# Sheet2.net
KiCad netlist of a schematic drawn in Altium Designer
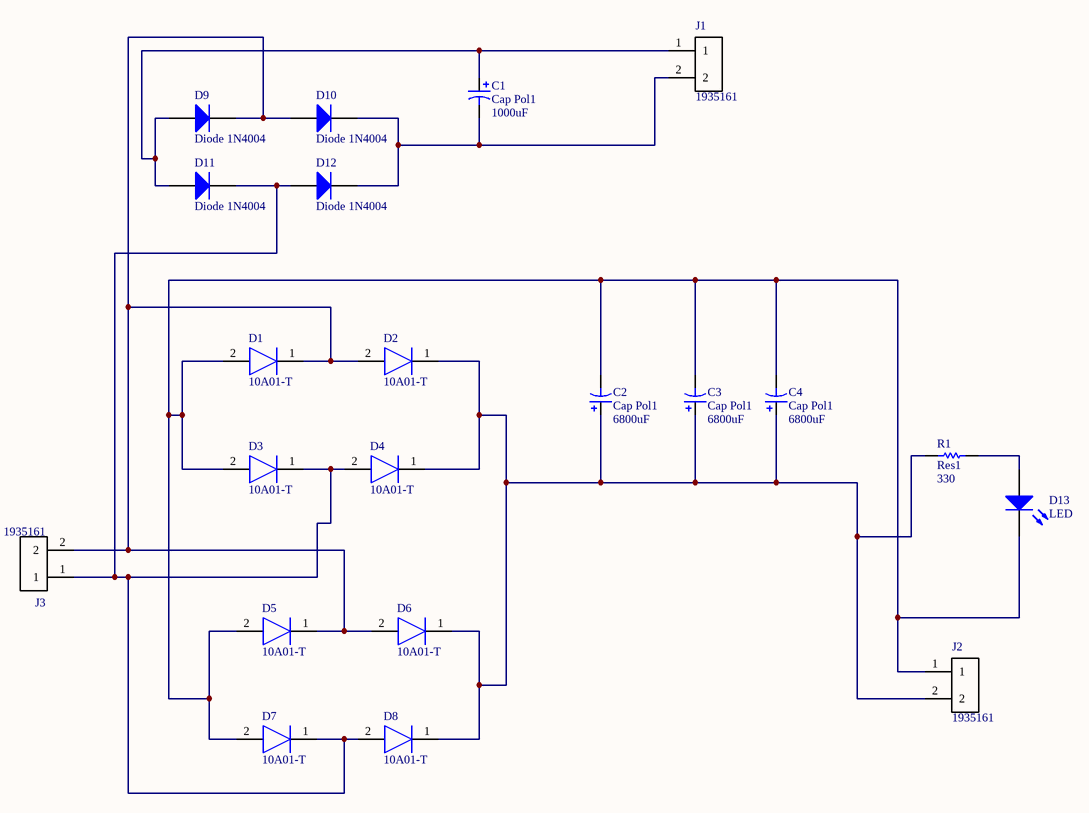
[diagram p0: Sheet2.SchDoc]

(export (version "E")
  (design (tool "Eeschema 10.0.6"))
  (components
    (comp (ref "C1")
      (value "Cap Pol1")
      (footprint "RB7.6-15")
      (description "Polarized Capacitor (Radial)")
      (fields (field (name "ALTIUM_VALUE") "1000uF") (field (name "PUBLISHER") "Altium Limited"))
      (libsource (lib "Miscellaneous Devices") (part "Cap Pol1"))
    )
    (comp (ref "C2")
      (value "Cap Pol1")
      (footprint "RB7.6-15")
      (description "Polarized Capacitor (Radial)")
      (fields (field (name "ALTIUM_VALUE") "6800uF") (field (name "PUBLISHER") "Altium Limited"))
      (libsource (lib "Miscellaneous Devices") (part "Cap Pol1"))
    )
    (comp (ref "C3")
      (value "Cap Pol1")
      (footprint "RB7.6-15")
      (description "Polarized Capacitor (Radial)")
      (fields (field (name "ALTIUM_VALUE") "6800uF") (field (name "PUBLISHER") "Altium Limited"))
      (libsource (lib "Miscellaneous Devices") (part "Cap Pol1"))
    )
    (comp (ref "C4")
      (value "Cap Pol1")
      (footprint "RB7.6-15")
      (description "Polarized Capacitor (Radial)")
      (fields (field (name "ALTIUM_VALUE") "6800uF") (field (name "PUBLISHER") "Altium Limited"))
      (libsource (lib "Miscellaneous Devices") (part "Cap Pol1"))
    )
    (comp (ref "D1")
      (value "10A01-T")
      (footprint "SamacSys:DIOAD4425W130L885D885")
      (description "Diode")
      (fields (field (name "MOUSER PART NUMBER") "621-10A01-T") (field (name "RS PART NUMBER") "9228248"))
      (libsource (lib "*") (part "10A01-T"))
    )
    (comp (ref "D2")
      (value "10A01-T")
      (footprint "SamacSys:DIOAD4425W130L885D885")
      (description "Diode")
      (fields (field (name "MOUSER PART NUMBER") "621-10A01-T") (field (name "RS PART NUMBER") "9228248"))
      (libsource (lib "*") (part "10A01-T"))
    )
    (comp (ref "D3")
      (value "10A01-T")
      (footprint "SamacSys:DIOAD4425W130L885D885")
      (description "Diode")
      (fields (field (name "MOUSER PART NUMBER") "621-10A01-T") (field (name "RS PART NUMBER") "9228248"))
      (libsource (lib "*") (part "10A01-T"))
    )
    (comp (ref "D4")
      (value "10A01-T")
      (footprint "SamacSys:DIOAD4425W130L885D885")
      (description "Diode")
      (fields (field (name "MOUSER PART NUMBER") "621-10A01-T") (field (name "RS PART NUMBER") "9228248"))
      (libsource (lib "*") (part "10A01-T"))
    )
    (comp (ref "D5")
      (value "10A01-T")
      (footprint "SamacSys:DIOAD4425W130L885D885")
      (description "Diode")
      (fields (field (name "MOUSER PART NUMBER") "621-10A01-T") (field (name "RS PART NUMBER") "9228248"))
      (libsource (lib "*") (part "10A01-T"))
    )
    (comp (ref "D6")
      (value "10A01-T")
      (footprint "SamacSys:DIOAD4425W130L885D885")
      (description "Diode")
      (fields (field (name "MOUSER PART NUMBER") "621-10A01-T") (field (name "RS PART NUMBER") "9228248"))
      (libsource (lib "*") (part "10A01-T"))
    )
    (comp (ref "D7")
      (value "10A01-T")
      (footprint "SamacSys:DIOAD4425W130L885D885")
      (description "Diode")
      (fields (field (name "MOUSER PART NUMBER") "621-10A01-T") (field (name "RS PART NUMBER") "9228248"))
      (libsource (lib "*") (part "10A01-T"))
    )
    (comp (ref "D8")
      (value "10A01-T")
      (footprint "SamacSys:DIOAD4425W130L885D885")
      (description "Diode")
      (fields (field (name "MOUSER PART NUMBER") "621-10A01-T") (field (name "RS PART NUMBER") "9228248"))
      (libsource (lib "*") (part "10A01-T"))
    )
    (comp (ref "D9")
      (value "Diode 1N4004")
      (footprint "DO-41")
      (description "1 Amp General Purpose Rectifier")
      (fields (field (name "PUBLISHER") "Altium Limited"))
      (libsource (lib "Miscellaneous Devices") (part "Diode 1N4004"))
    )
    (comp (ref "D10")
      (value "Diode 1N4004")
      (footprint "DO-41")
      (description "1 Amp General Purpose Rectifier")
      (fields (field (name "PUBLISHER") "Altium Limited"))
      (libsource (lib "Miscellaneous Devices") (part "Diode 1N4004"))
    )
    (comp (ref "D11")
      (value "Diode 1N4004")
      (footprint "DO-41")
      (description "1 Amp General Purpose Rectifier")
      (fields (field (name "PUBLISHER") "Altium Limited"))
      (libsource (lib "Miscellaneous Devices") (part "Diode 1N4004"))
    )
    (comp (ref "D12")
      (value "Diode 1N4004")
      (footprint "DO-41")
      (description "1 Amp General Purpose Rectifier")
      (fields (field (name "PUBLISHER") "Altium Limited"))
      (libsource (lib "Miscellaneous Devices") (part "Diode 1N4004"))
    )
    (comp (ref "D13")
      (value "LED")
      (footprint "LED-1")
      (description "Typical RED GaAs LED")
      (fields (field (name "PUBLISHER") "Altium Limited"))
      (libsource (lib "Miscellaneous Devices") (part "LED1"))
    )
    (comp (ref "J1")
      (value "1935161")
      (footprint "*PHOENIX_1935161")
      (description "Conn Terminal Blocks 2 POS 5mm Solder ST Thru-Hole 16A")
      (fields (field (name "MF") "Phoenix Contact"))
      (libsource (lib "1935161") (part "1935161"))
    )
    (comp (ref "J2")
      (value "1935161")
      (footprint "*PHOENIX_1935161")
      (description "Conn Terminal Blocks 2 POS 5mm Solder ST Thru-Hole 16A")
      (fields (field (name "MF") "Phoenix Contact"))
      (libsource (lib "1935161") (part "1935161"))
    )
    (comp (ref "J3")
      (value "1935161")
      (footprint "*PHOENIX_1935161")
      (description "Conn Terminal Blocks 2 POS 5mm Solder ST Thru-Hole 16A")
      (fields (field (name "MF") "Phoenix Contact"))
      (libsource (lib "1935161") (part "1935161"))
    )
    (comp (ref "R1")
      (value "Res1")
      (footprint "AXIAL-0.3")
      (description "Resistor")
      (fields (field (name "ALTIUM_VALUE") "330") (field (name "PUBLISHER") "Altium Limited"))
      (libsource (lib "Miscellaneous Devices") (part "Res1"))
    )
  )
  (nets
    (net (code "1") (name "Net-(D1-A)") (class "Default")
      (node (ref "C2") (pin "2") (pinfunction "2_2") (pintype "passive"))
      (node (ref "C3") (pin "2") (pinfunction "2_2") (pintype "passive"))
      (node (ref "C4") (pin "2") (pinfunction "2_2") (pintype "passive"))
      (node (ref "D1") (pin "2") (pinfunction "A_2") (pintype "passive"))
      (node (ref "D13") (pin "2") (pinfunction "K_2") (pintype "passive"))
      (node (ref "D3") (pin "2") (pinfunction "A_2") (pintype "passive"))
      (node (ref "D5") (pin "2") (pinfunction "A_2") (pintype "passive"))
      (node (ref "D7") (pin "2") (pinfunction "A_2") (pintype "passive"))
      (node (ref "J2") (pin "1") (pinfunction "1_1") (pintype "passive"))
    )
    (net (code "2") (name "Net-(D1-K)") (class "Default")
      (node (ref "D1") (pin "1") (pinfunction "K_1") (pintype "passive"))
      (node (ref "D10") (pin "1") (pinfunction "A_1") (pintype "passive"))
      (node (ref "D2") (pin "2") (pinfunction "A_2") (pintype "passive"))
      (node (ref "D5") (pin "1") (pinfunction "K_1") (pintype "passive"))
      (node (ref "D6") (pin "2") (pinfunction "A_2") (pintype "passive"))
      (node (ref "D9") (pin "2") (pinfunction "K_2") (pintype "passive"))
      (node (ref "J3") (pin "2") (pinfunction "2_2") (pintype "passive"))
    )
    (net (code "3") (name "Net-(D2-K)") (class "Default")
      (node (ref "C2") (pin "1") (pinfunction "1_1") (pintype "passive"))
      (node (ref "C3") (pin "1") (pinfunction "1_1") (pintype "passive"))
      (node (ref "C4") (pin "1") (pinfunction "1_1") (pintype "passive"))
      (node (ref "D2") (pin "1") (pinfunction "K_1") (pintype "passive"))
      (node (ref "D4") (pin "1") (pinfunction "K_1") (pintype "passive"))
      (node (ref "D6") (pin "1") (pinfunction "K_1") (pintype "passive"))
      (node (ref "D8") (pin "1") (pinfunction "K_1") (pintype "passive"))
      (node (ref "J2") (pin "2") (pinfunction "2_2") (pintype "passive"))
      (node (ref "R1") (pin "1") (pinfunction "1_1") (pintype "passive"))
    )
    (net (code "4") (name "Net-(D10-K)") (class "Default")
      (node (ref "C1") (pin "2") (pinfunction "2_2") (pintype "passive"))
      (node (ref "D10") (pin "2") (pinfunction "K_2") (pintype "passive"))
      (node (ref "D12") (pin "2") (pinfunction "K_2") (pintype "passive"))
      (node (ref "J1") (pin "2") (pinfunction "2_2") (pintype "passive"))
    )
    (net (code "5") (name "Net-(D11-A)") (class "Default")
      (node (ref "C1") (pin "1") (pinfunction "1_1") (pintype "passive"))
      (node (ref "D11") (pin "1") (pinfunction "A_1") (pintype "passive"))
      (node (ref "D9") (pin "1") (pinfunction "A_1") (pintype "passive"))
      (node (ref "J1") (pin "1") (pinfunction "1_1") (pintype "passive"))
    )
    (net (code "6") (name "Net-(D11-K)") (class "Default")
      (node (ref "D11") (pin "2") (pinfunction "K_2") (pintype "passive"))
      (node (ref "D12") (pin "1") (pinfunction "A_1") (pintype "passive"))
      (node (ref "D3") (pin "1") (pinfunction "K_1") (pintype "passive"))
      (node (ref "D4") (pin "2") (pinfunction "A_2") (pintype "passive"))
      (node (ref "D7") (pin "1") (pinfunction "K_1") (pintype "passive"))
      (node (ref "D8") (pin "2") (pinfunction "A_2") (pintype "passive"))
      (node (ref "J3") (pin "1") (pinfunction "1_1") (pintype "passive"))
    )
    (net (code "7") (name "Net-(D13-A)") (class "Default")
      (node (ref "D13") (pin "1") (pinfunction "A_1") (pintype "passive"))
      (node (ref "R1") (pin "2") (pinfunction "2_2") (pintype "passive"))
    )
  )
)
